# power_electronics.net
KiCad netlist of a schematic drawn in EAGLE
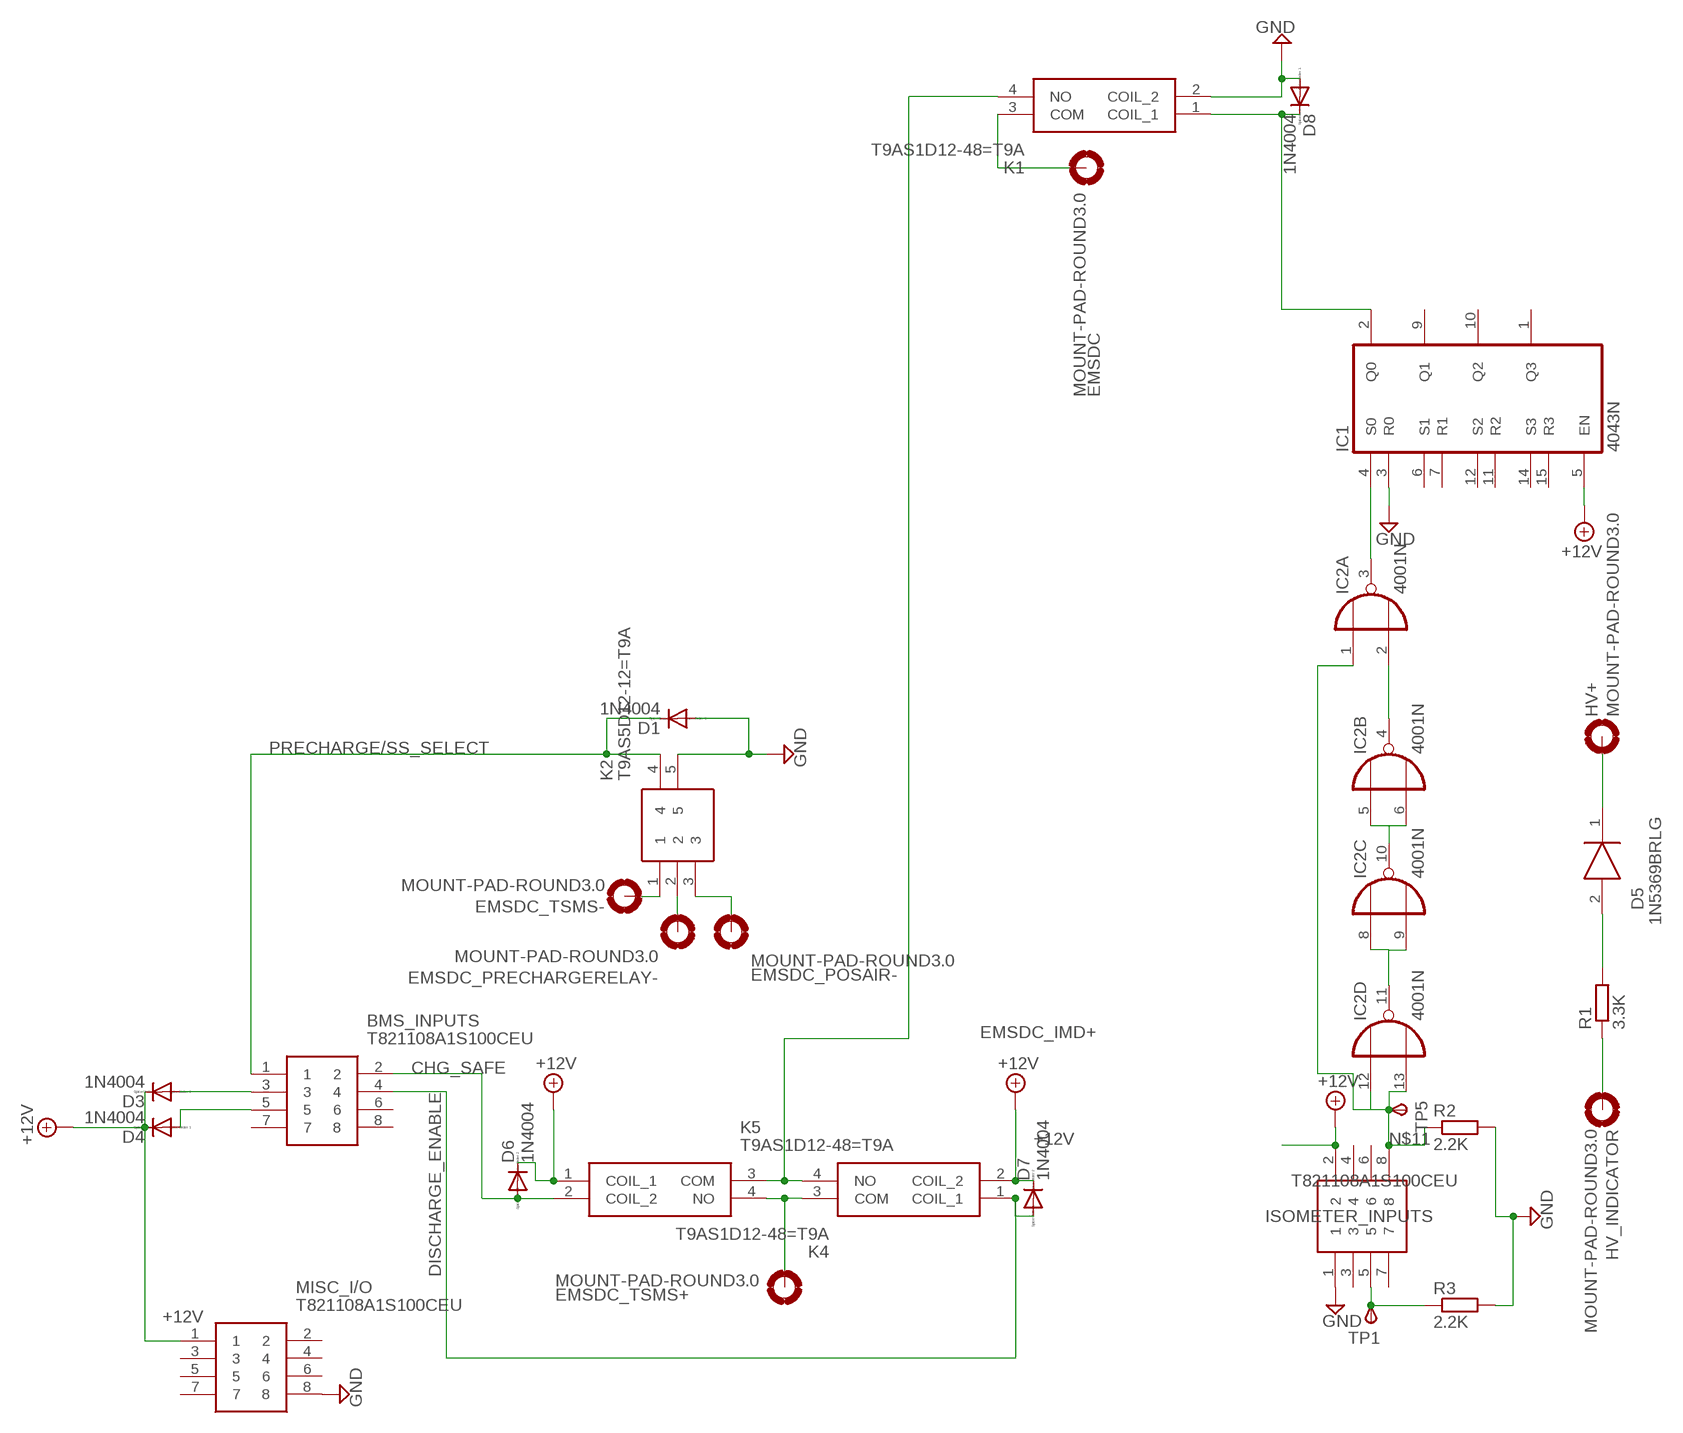
[diagram p0: schematic, sheet 1]

(export (version "E")
  (design (tool "Eeschema 10.0.6"))
  (components
    (comp (ref "BMS_INPUTS")
      (value "T821108A1S100CEU")
      (footprint "eagle-import:HDRV8W64P254_2X4_1778X895X915P")
      (fields (field (name "RS_PART_NUMBER") "8323569"))
      (libsource (lib "eagle-import") (part "T821108A1S100CEU"))
    )
    (comp (ref "D1")
      (value "1N4004")
      (footprint "eagle-import:DO41-10")
      (libsource (lib "eagle-import") (part "1N4004"))
    )
    (comp (ref "D3")
      (value "1N4004")
      (footprint "eagle-import:DO41-10")
      (libsource (lib "eagle-import") (part "1N4004"))
    )
    (comp (ref "D4")
      (value "1N4004")
      (footprint "eagle-import:DO41-10")
      (libsource (lib "eagle-import") (part "1N4004"))
    )
    (comp (ref "D5")
      (value "1N5369BRLG")
      (footprint "eagle-import:DIOAD2260W109L864D349")
      (fields (field (name "RS_PART_NUMBER") "6547678P"))
      (libsource (lib "eagle-import") (part "1N5369BRLG"))
    )
    (comp (ref "D6")
      (value "1N4004")
      (footprint "eagle-import:DO41-10")
      (libsource (lib "eagle-import") (part "1N4004"))
    )
    (comp (ref "D7")
      (value "1N4004")
      (footprint "eagle-import:DO41-10")
      (libsource (lib "eagle-import") (part "1N4004"))
    )
    (comp (ref "D8")
      (value "1N4004")
      (footprint "eagle-import:DO41-10")
      (libsource (lib "eagle-import") (part "1N4004"))
    )
    (comp (ref "EMSDC")
      (value "MOUNT-PAD-ROUND3.0")
      (footprint "eagle-import:3,0-PAD")
      (libsource (lib "eagle-import") (part "MOUNT-PAD-ROUND3.0"))
    )
    (comp (ref "EMSDC_POSAIR-")
      (value "MOUNT-PAD-ROUND3.0")
      (footprint "eagle-import:3,0-PAD")
      (libsource (lib "eagle-import") (part "MOUNT-PAD-ROUND3.0"))
    )
    (comp (ref "EMSDC_PRECHARGERELAY-")
      (value "MOUNT-PAD-ROUND3.0")
      (footprint "eagle-import:3,0-PAD")
      (libsource (lib "eagle-import") (part "MOUNT-PAD-ROUND3.0"))
    )
    (comp (ref "EMSDC_TSMS+")
      (value "MOUNT-PAD-ROUND3.0")
      (footprint "eagle-import:3,0-PAD")
      (libsource (lib "eagle-import") (part "MOUNT-PAD-ROUND3.0"))
    )
    (comp (ref "EMSDC_TSMS-")
      (value "MOUNT-PAD-ROUND3.0")
      (footprint "eagle-import:3,0-PAD")
      (libsource (lib "eagle-import") (part "MOUNT-PAD-ROUND3.0"))
    )
    (comp (ref "HV+")
      (value "MOUNT-PAD-ROUND3.0")
      (footprint "eagle-import:3,0-PAD")
      (libsource (lib "eagle-import") (part "MOUNT-PAD-ROUND3.0"))
    )
    (comp (ref "HV_INDICATOR")
      (value "MOUNT-PAD-ROUND3.0")
      (footprint "eagle-import:3,0-PAD")
      (libsource (lib "eagle-import") (part "MOUNT-PAD-ROUND3.0"))
    )
    (comp (ref "IC1")
      (value "4043N")
      (footprint "eagle-import:DIL16")
      (libsource (lib "eagle-import") (part "4043N"))
    )
    (comp (ref "IC2")
      (value "4001N")
      (footprint "eagle-import:DIL14")
      (libsource (lib "eagle-import") (part "4001N"))
    )
    (comp (ref "ISOMETER_INPUTS")
      (value "T821108A1S100CEU")
      (footprint "eagle-import:HDRV8W64P254_2X4_1778X895X915P")
      (fields (field (name "RS_PART_NUMBER") "8323569"))
      (libsource (lib "eagle-import") (part "T821108A1S100CEU"))
    )
    (comp (ref "K1")
      (value "T9AS1D12-48=T9A")
      (footprint "eagle-import:T9AS1D1248T9A")
      (fields (field (name "RS_PART_NUMBER") "6802534P"))
      (libsource (lib "eagle-import") (part "T9AS1D12-48=T9A"))
    )
    (comp (ref "K2")
      (value "T9AS5D12-12=T9A")
      (footprint "eagle-import:T9AS1D12")
      (fields (field (name "RS_PART_NUMBER") "6802528"))
      (libsource (lib "eagle-import") (part "T9AS5D12-12=T9A"))
    )
    (comp (ref "K4")
      (value "T9AS1D12-48=T9A")
      (footprint "eagle-import:T9AS1D1248T9A")
      (fields (field (name "RS_PART_NUMBER") "6802534P"))
      (libsource (lib "eagle-import") (part "T9AS1D12-48=T9A"))
    )
    (comp (ref "K5")
      (value "T9AS1D12-48=T9A")
      (footprint "eagle-import:T9AS1D1248T9A")
      (fields (field (name "RS_PART_NUMBER") "6802534P"))
      (libsource (lib "eagle-import") (part "T9AS1D12-48=T9A"))
    )
    (comp (ref "MISC_I/O")
      (value "T821108A1S100CEU")
      (footprint "eagle-import:HDRV8W64P254_2X4_1778X895X915P")
      (fields (field (name "RS_PART_NUMBER") "8323569"))
      (libsource (lib "eagle-import") (part "T821108A1S100CEU"))
    )
    (comp (ref "R1")
      (value "3.3K")
      (footprint "eagle-import:0207_15")
      (libsource (lib "eagle-import") (part "R-EU_0207/15"))
    )
    (comp (ref "R2")
      (value "2.2K")
      (footprint "eagle-import:0207_12")
      (libsource (lib "eagle-import") (part "R-EU_0207/12"))
    )
    (comp (ref "R3")
      (value "2.2K")
      (footprint "eagle-import:0207_12")
      (libsource (lib "eagle-import") (part "R-EU_0207/12"))
    )
    (comp (ref "TP1")
      (value "TPSPAD1-17")
      (footprint "eagle-import:P1-17")
      (libsource (lib "eagle-import") (part "TPSPAD1-17"))
    )
    (comp (ref "TP5")
      (value "TPSPAD1-17")
      (footprint "eagle-import:P1-17")
      (libsource (lib "eagle-import") (part "TPSPAD1-17"))
    )
  )
  (nets
    (net (code "1") (name "+12V") (class "Default")
      (node (ref "D3") (pin "C") (pinfunction "C_C") (pintype "passive"))
      (node (ref "D4") (pin "C") (pinfunction "C_C") (pintype "passive"))
      (node (ref "D6") (pin "C") (pinfunction "C_C") (pintype "passive"))
      (node (ref "D7") (pin "C") (pinfunction "C_C") (pintype "passive"))
      (node (ref "IC1") (pin "5") (pinfunction "EN_5") (pintype "input"))
      (node (ref "ISOMETER_INPUTS") (pin "2") (pinfunction "2_2") (pintype "bidirectional"))
      (node (ref "K4") (pin "2") (pinfunction "COIL_2_2") (pintype "bidirectional"))
      (node (ref "K5") (pin "1") (pinfunction "COIL_1_1") (pintype "bidirectional"))
      (node (ref "MISC_I/O") (pin "1") (pinfunction "1_1") (pintype "bidirectional"))
    )
    (net (code "2") (name "/CHG_SAFE") (class "Default")
      (node (ref "BMS_INPUTS") (pin "2") (pinfunction "2_2") (pintype "bidirectional"))
      (node (ref "D6") (pin "A") (pinfunction "A_A") (pintype "passive"))
      (node (ref "K5") (pin "2") (pinfunction "COIL_2_2") (pintype "bidirectional"))
    )
    (net (code "3") (name "/DISCHARGE_ENABLE") (class "Default")
      (node (ref "BMS_INPUTS") (pin "4") (pinfunction "4_4") (pintype "bidirectional"))
      (node (ref "D7") (pin "A") (pinfunction "A_A") (pintype "passive"))
      (node (ref "K4") (pin "1") (pinfunction "COIL_1_1") (pintype "bidirectional"))
    )
    (net (code "4") (name "/EMSDC_IMD+") (class "Default")
      (node (ref "K1") (pin "4") (pinfunction "NO_4") (pintype "bidirectional"))
      (node (ref "K4") (pin "4") (pinfunction "NO_4") (pintype "bidirectional"))
      (node (ref "K5") (pin "3") (pinfunction "COM_3") (pintype "bidirectional"))
    )
    (net (code "5") (name "/N$11") (class "Default")
      (node (ref "IC2") (pin "1") (pinfunction "I0_1") (pintype "input"))
      (node (ref "IC2") (pin "12") (pinfunction "I0_12") (pintype "input"))
      (node (ref "IC2") (pin "13") (pinfunction "I1_13") (pintype "input"))
      (node (ref "ISOMETER_INPUTS") (pin "8") (pinfunction "8_8") (pintype "bidirectional"))
      (node (ref "R2") (pin "1") (pinfunction "1_1") (pintype "passive"))
      (node (ref "TP5") (pin "TP") (pinfunction "PP_TP") (pintype "input"))
    )
    (net (code "6") (name "/PRECHARGE{slash}SS_SELECT") (class "Default")
      (node (ref "BMS_INPUTS") (pin "1") (pinfunction "1_1") (pintype "bidirectional"))
      (node (ref "D1") (pin "C") (pinfunction "C_C") (pintype "passive"))
      (node (ref "K2") (pin "4") (pinfunction "4_4") (pintype "bidirectional"))
    )
    (net (code "7") (name "GND") (class "Default")
      (node (ref "D1") (pin "A") (pinfunction "A_A") (pintype "passive"))
      (node (ref "D8") (pin "A") (pinfunction "A_A") (pintype "passive"))
      (node (ref "IC1") (pin "3") (pinfunction "R0_3") (pintype "input"))
      (node (ref "ISOMETER_INPUTS") (pin "1") (pinfunction "1_1") (pintype "bidirectional"))
      (node (ref "K1") (pin "2") (pinfunction "COIL_2_2") (pintype "bidirectional"))
      (node (ref "K2") (pin "5") (pinfunction "5_5") (pintype "bidirectional"))
      (node (ref "MISC_I/O") (pin "8") (pinfunction "8_8") (pintype "bidirectional"))
      (node (ref "R2") (pin "2") (pinfunction "2_2") (pintype "passive"))
      (node (ref "R3") (pin "2") (pinfunction "2_2") (pintype "passive"))
    )
    (net (code "8") (name "Net-(BMS_INPUTS-Pad3)") (class "Default")
      (node (ref "BMS_INPUTS") (pin "3") (pinfunction "3_3") (pintype "bidirectional"))
      (node (ref "D3") (pin "A") (pinfunction "A_A") (pintype "passive"))
    )
    (net (code "9") (name "Net-(BMS_INPUTS-Pad5)") (class "Default")
      (node (ref "BMS_INPUTS") (pin "5") (pinfunction "5_5") (pintype "bidirectional"))
      (node (ref "D4") (pin "A") (pinfunction "A_A") (pintype "passive"))
    )
    (net (code "10") (name "Net-(D5-A)") (class "Default")
      (node (ref "D5") (pin "2") (pinfunction "A_2") (pintype "bidirectional"))
      (node (ref "R1") (pin "2") (pinfunction "2_2") (pintype "passive"))
    )
    (net (code "11") (name "Net-(D5-K)") (class "Default")
      (node (ref "D5") (pin "1") (pinfunction "K_1") (pintype "bidirectional"))
      (node (ref "HV+") (pin "B3,0") (pinfunction "MOUNT_B3,0") (pintype "passive"))
    )
    (net (code "12") (name "Net-(EMSDC-MOUNT)") (class "Default")
      (node (ref "EMSDC") (pin "B3,0") (pinfunction "MOUNT_B3,0") (pintype "passive"))
      (node (ref "K1") (pin "3") (pinfunction "COM_3") (pintype "bidirectional"))
    )
    (net (code "13") (name "Net-(EMSDC_POSAIR--MOUNT)") (class "Default")
      (node (ref "EMSDC_POSAIR-") (pin "B3,0") (pinfunction "MOUNT_B3,0") (pintype "passive"))
      (node (ref "K2") (pin "3") (pinfunction "3_3") (pintype "bidirectional"))
    )
    (net (code "14") (name "Net-(EMSDC_PRECHARGERELAY--MOUNT)") (class "Default")
      (node (ref "EMSDC_PRECHARGERELAY-") (pin "B3,0") (pinfunction "MOUNT_B3,0") (pintype "passive"))
      (node (ref "K2") (pin "2") (pinfunction "2_2") (pintype "bidirectional"))
    )
    (net (code "15") (name "Net-(EMSDC_TSMS+-MOUNT)") (class "Default")
      (node (ref "EMSDC_TSMS+") (pin "B3,0") (pinfunction "MOUNT_B3,0") (pintype "passive"))
      (node (ref "K4") (pin "3") (pinfunction "COM_3") (pintype "bidirectional"))
      (node (ref "K5") (pin "4") (pinfunction "NO_4") (pintype "bidirectional"))
    )
    (net (code "16") (name "Net-(EMSDC_TSMS--MOUNT)") (class "Default")
      (node (ref "EMSDC_TSMS-") (pin "B3,0") (pinfunction "MOUNT_B3,0") (pintype "passive"))
      (node (ref "K2") (pin "1") (pinfunction "1_1") (pintype "bidirectional"))
    )
    (net (code "17") (name "Net-(HV_INDICATOR-MOUNT)") (class "Default")
      (node (ref "HV_INDICATOR") (pin "B3,0") (pinfunction "MOUNT_B3,0") (pintype "passive"))
      (node (ref "R1") (pin "1") (pinfunction "1_1") (pintype "passive"))
    )
    (net (code "18") (name "Net-(IC1A-Q0)") (class "Default")
      (node (ref "D8") (pin "C") (pinfunction "C_C") (pintype "passive"))
      (node (ref "IC1") (pin "2") (pinfunction "Q0_2") (pintype "output"))
      (node (ref "K1") (pin "1") (pinfunction "COIL_1_1") (pintype "bidirectional"))
    )
    (net (code "19") (name "Net-(IC1A-S0)") (class "Default")
      (node (ref "IC1") (pin "4") (pinfunction "S0_4") (pintype "input"))
      (node (ref "IC2") (pin "3") (pinfunction "O_3") (pintype "output"))
    )
    (net (code "20") (name "Net-(IC2A-I1)") (class "Default")
      (node (ref "IC2") (pin "2") (pinfunction "I1_2") (pintype "input"))
      (node (ref "IC2") (pin "4") (pinfunction "O_4") (pintype "output"))
    )
    (net (code "21") (name "Net-(IC2B-I0)") (class "Default")
      (node (ref "IC2") (pin "10") (pinfunction "O_10") (pintype "output"))
      (node (ref "IC2") (pin "5") (pinfunction "I0_5") (pintype "input"))
      (node (ref "IC2") (pin "6") (pinfunction "I1_6") (pintype "input"))
    )
    (net (code "22") (name "Net-(IC2C-I0)") (class "Default")
      (node (ref "IC2") (pin "11") (pinfunction "O_11") (pintype "output"))
      (node (ref "IC2") (pin "8") (pinfunction "I0_8") (pintype "input"))
      (node (ref "IC2") (pin "9") (pinfunction "I1_9") (pintype "input"))
    )
    (net (code "23") (name "Net-(TP1-PP)") (class "Default")
      (node (ref "ISOMETER_INPUTS") (pin "5") (pinfunction "5_5") (pintype "bidirectional"))
      (node (ref "R3") (pin "1") (pinfunction "1_1") (pintype "passive"))
      (node (ref "TP1") (pin "TP") (pinfunction "PP_TP") (pintype "input"))
    )
    (net (code "24") (name "unconnected-(BMS_INPUTS-Pad6)") (class "Default")
      (node (ref "BMS_INPUTS") (pin "6") (pinfunction "6_6") (pintype "bidirectional"))
    )
    (net (code "25") (name "unconnected-(BMS_INPUTS-Pad7)") (class "Default")
      (node (ref "BMS_INPUTS") (pin "7") (pinfunction "7_7") (pintype "bidirectional"))
    )
    (net (code "26") (name "unconnected-(BMS_INPUTS-Pad8)") (class "Default")
      (node (ref "BMS_INPUTS") (pin "8") (pinfunction "8_8") (pintype "bidirectional"))
    )
    (net (code "27") (name "unconnected-(IC1A-Q1-Pad9)") (class "Default")
      (node (ref "IC1") (pin "9") (pinfunction "Q1_9") (pintype "output"))
    )
    (net (code "28") (name "unconnected-(IC1A-Q2-Pad10)") (class "Default")
      (node (ref "IC1") (pin "10") (pinfunction "Q2_10") (pintype "output"))
    )
    (net (code "29") (name "unconnected-(IC1A-Q3-Pad1)") (class "Default")
      (node (ref "IC1") (pin "1") (pinfunction "Q3_1") (pintype "output"))
    )
    (net (code "30") (name "unconnected-(IC1A-R1-Pad7)") (class "Default")
      (node (ref "IC1") (pin "7") (pinfunction "R1_7") (pintype "input"))
    )
    (net (code "31") (name "unconnected-(IC1A-R2-Pad11)") (class "Default")
      (node (ref "IC1") (pin "11") (pinfunction "R2_11") (pintype "input"))
    )
    (net (code "32") (name "unconnected-(IC1A-R3-Pad15)") (class "Default")
      (node (ref "IC1") (pin "15") (pinfunction "R3_15") (pintype "input"))
    )
    (net (code "33") (name "unconnected-(IC1A-S1-Pad6)") (class "Default")
      (node (ref "IC1") (pin "6") (pinfunction "S1_6") (pintype "input"))
    )
    (net (code "34") (name "unconnected-(IC1A-S2-Pad12)") (class "Default")
      (node (ref "IC1") (pin "12") (pinfunction "S2_12") (pintype "input"))
    )
    (net (code "35") (name "unconnected-(IC1A-S3-Pad14)") (class "Default")
      (node (ref "IC1") (pin "14") (pinfunction "S3_14") (pintype "input"))
    )
    (net (code "36") (name "unconnected-(ISOMETER_INPUTS-Pad3)") (class "Default")
      (node (ref "ISOMETER_INPUTS") (pin "3") (pinfunction "3_3") (pintype "bidirectional"))
    )
    (net (code "37") (name "unconnected-(ISOMETER_INPUTS-Pad4)") (class "Default")
      (node (ref "ISOMETER_INPUTS") (pin "4") (pinfunction "4_4") (pintype "bidirectional"))
    )
    (net (code "38") (name "unconnected-(ISOMETER_INPUTS-Pad6)") (class "Default")
      (node (ref "ISOMETER_INPUTS") (pin "6") (pinfunction "6_6") (pintype "bidirectional"))
    )
    (net (code "39") (name "unconnected-(ISOMETER_INPUTS-Pad7)") (class "Default")
      (node (ref "ISOMETER_INPUTS") (pin "7") (pinfunction "7_7") (pintype "bidirectional"))
    )
    (net (code "40") (name "unconnected-(MISC_I/O-Pad2)") (class "Default")
      (node (ref "MISC_I/O") (pin "2") (pinfunction "2_2") (pintype "bidirectional"))
    )
    (net (code "41") (name "unconnected-(MISC_I/O-Pad3)") (class "Default")
      (node (ref "MISC_I/O") (pin "3") (pinfunction "3_3") (pintype "bidirectional"))
    )
    (net (code "42") (name "unconnected-(MISC_I/O-Pad4)") (class "Default")
      (node (ref "MISC_I/O") (pin "4") (pinfunction "4_4") (pintype "bidirectional"))
    )
    (net (code "43") (name "unconnected-(MISC_I/O-Pad5)") (class "Default")
      (node (ref "MISC_I/O") (pin "5") (pinfunction "5_5") (pintype "bidirectional"))
    )
    (net (code "44") (name "unconnected-(MISC_I/O-Pad6)") (class "Default")
      (node (ref "MISC_I/O") (pin "6") (pinfunction "6_6") (pintype "bidirectional"))
    )
    (net (code "45") (name "unconnected-(MISC_I/O-Pad7)") (class "Default")
      (node (ref "MISC_I/O") (pin "7") (pinfunction "7_7") (pintype "bidirectional"))
    )
  )
)
